# Module_Current_Probe_v2.net
KiCad netlist of a schematic drawn in EAGLE
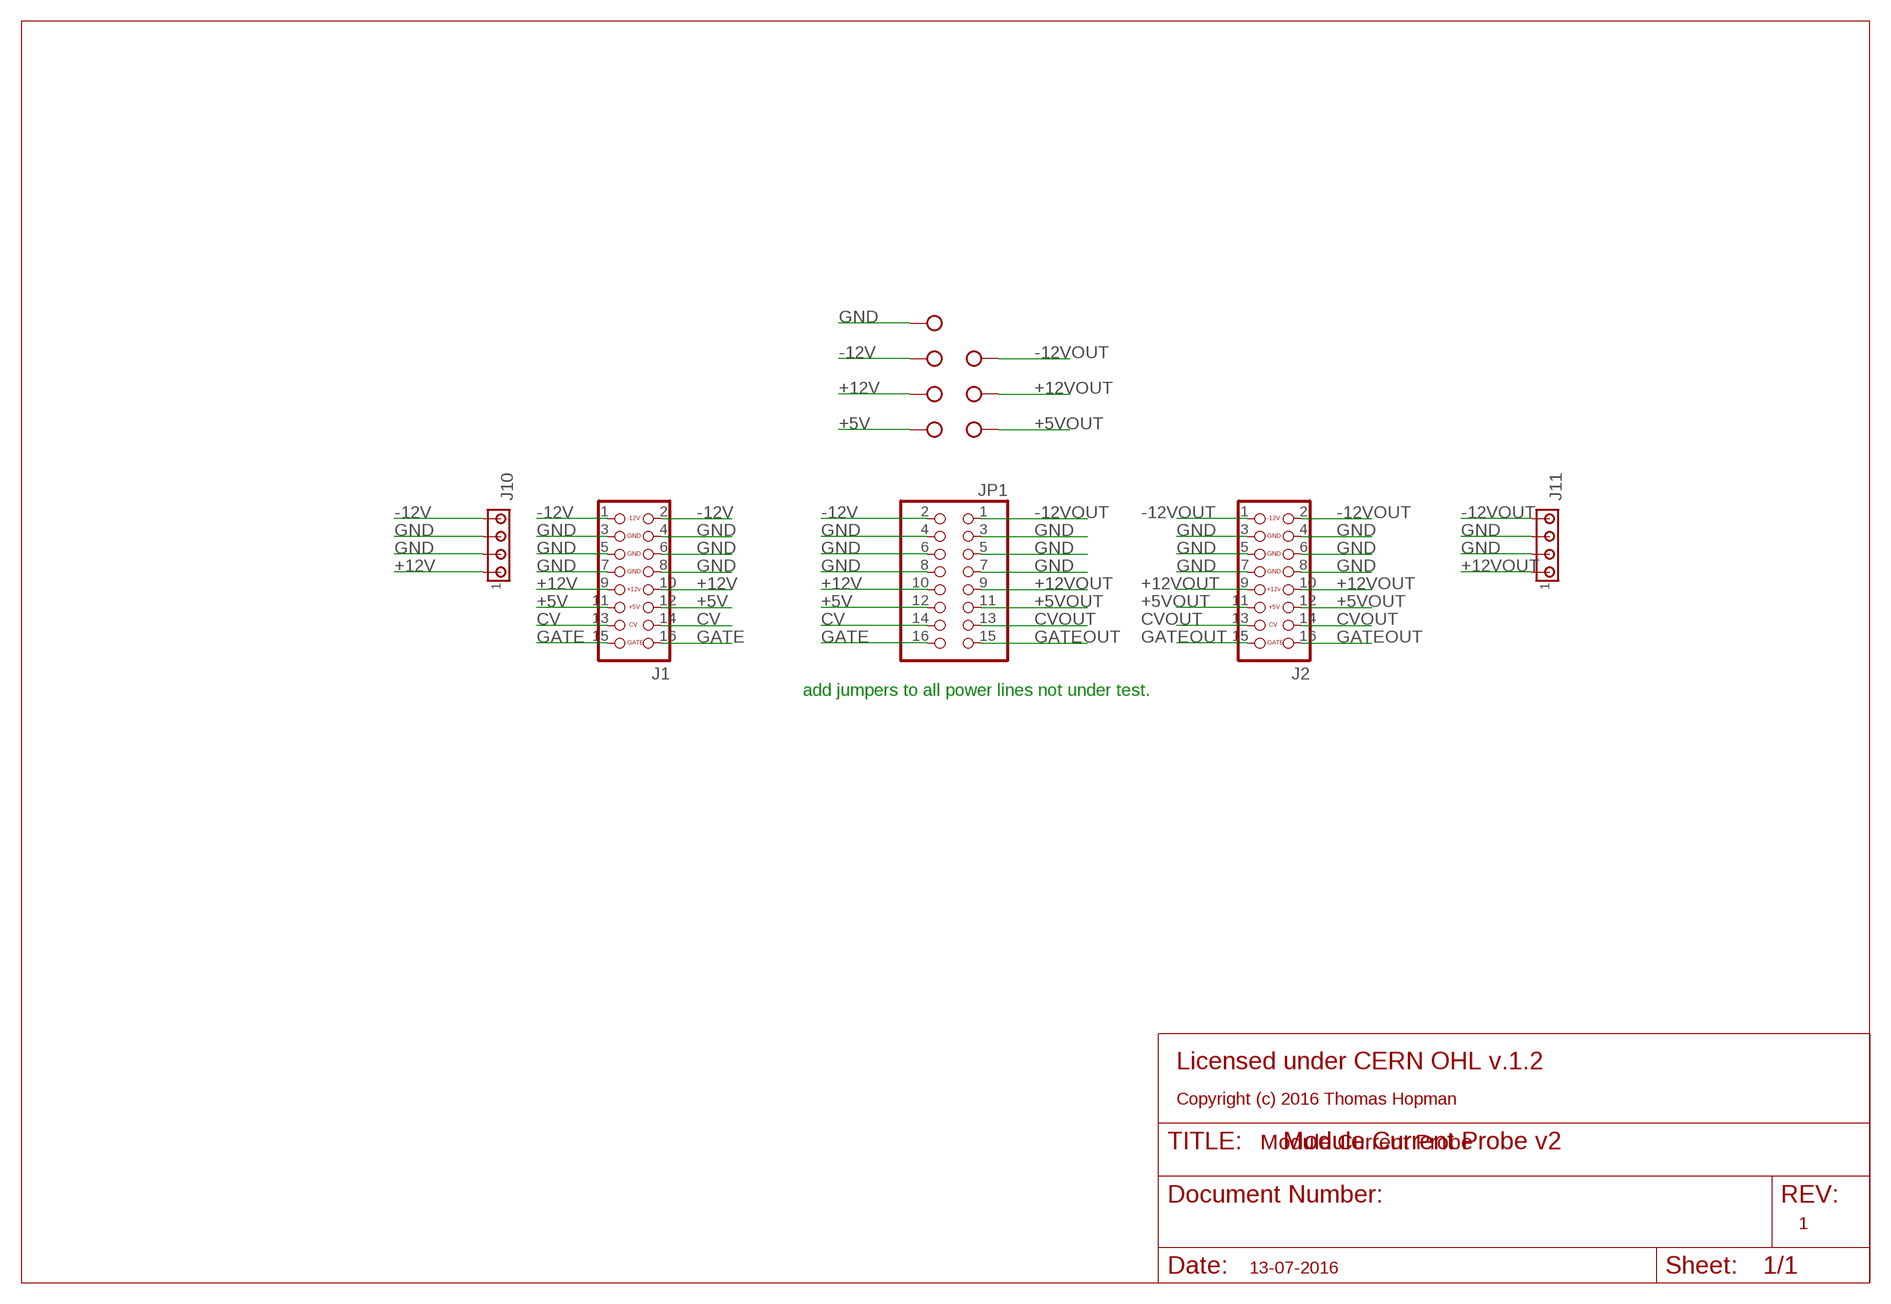
[diagram p0: schematic, sheet 1]

(export (version "E")
  (design (tool "Eeschema 10.0.6"))
  (components
    (comp (ref "J1")
      (value "CON_HEADER_2X08-PTH-SHROUDED")
      (footprint "eagle-import:PINSHRD_PTH_2X08")
      (libsource (lib "eagle-import") (part "CON_HEADER_2X08-PTH-SHROUDED"))
    )
    (comp (ref "J2")
      (value "CON_HEADER_2X08-PTH-SHROUDED")
      (footprint "eagle-import:PINSHRD_PTH_2X08")
      (libsource (lib "eagle-import") (part "CON_HEADER_2X08-PTH-SHROUDED"))
    )
    (comp (ref "J3")
      (value "BANANA-JACK")
      (footprint "eagle-import:BANANA-PRINT")
      (libsource (lib "eagle-import") (part "BANANA-JACK"))
    )
    (comp (ref "J4")
      (value "BANANA-JACK")
      (footprint "eagle-import:BANANA-PRINT")
      (libsource (lib "eagle-import") (part "BANANA-JACK"))
    )
    (comp (ref "J5")
      (value "BANANA-JACK")
      (footprint "eagle-import:BANANA-PRINT")
      (libsource (lib "eagle-import") (part "BANANA-JACK"))
    )
    (comp (ref "J6")
      (value "BANANA-JACK")
      (footprint "eagle-import:BANANA-PRINT")
      (libsource (lib "eagle-import") (part "BANANA-JACK"))
    )
    (comp (ref "J7")
      (value "BANANA-JACK")
      (footprint "eagle-import:BANANA-PRINT")
      (libsource (lib "eagle-import") (part "BANANA-JACK"))
    )
    (comp (ref "J8")
      (value "BANANA-JACK")
      (footprint "eagle-import:BANANA-PRINT")
      (libsource (lib "eagle-import") (part "BANANA-JACK"))
    )
    (comp (ref "J9")
      (value "BANANA-JACK")
      (footprint "eagle-import:BANANA-PRINT")
      (libsource (lib "eagle-import") (part "BANANA-JACK"))
    )
    (comp (ref "J10")
      (value "MTA04-156")
      (footprint "eagle-import:1X4MTA")
      (libsource (lib "eagle-import") (part "MTA04-156"))
    )
    (comp (ref "J11")
      (value "MTA04-156")
      (footprint "eagle-import:1X4MTA")
      (libsource (lib "eagle-import") (part "MTA04-156"))
    )
    (comp (ref "JP1")
      (value "PINHD-2X8")
      (footprint "eagle-import:2X08")
      (libsource (lib "eagle-import") (part "PINHD-2X8"))
    )
  )
  (nets
    (net (code "1") (name "/+5V") (class "Default")
      (node (ref "J1") (pin "11") (pinfunction "11_11") (pintype "passive"))
      (node (ref "J1") (pin "12") (pinfunction "12_12") (pintype "passive"))
      (node (ref "J5") (pin "P$1") (pinfunction "PIN_P$1") (pintype "bidirectional"))
      (node (ref "JP1") (pin "12") (pinfunction "12_12") (pintype "passive"))
    )
    (net (code "2") (name "/+5VOUT") (class "Default")
      (node (ref "J2") (pin "11") (pinfunction "11_11") (pintype "passive"))
      (node (ref "J2") (pin "12") (pinfunction "12_12") (pintype "passive"))
      (node (ref "J8") (pin "P$1") (pinfunction "PIN_P$1") (pintype "bidirectional"))
      (node (ref "JP1") (pin "11") (pinfunction "11_11") (pintype "passive"))
    )
    (net (code "3") (name "/+12V") (class "Default")
      (node (ref "J1") (pin "10") (pinfunction "10_10") (pintype "passive"))
      (node (ref "J1") (pin "9") (pinfunction "9_9") (pintype "passive"))
      (node (ref "J10") (pin "1") (pinfunction "1_1") (pintype "passive"))
      (node (ref "J4") (pin "P$1") (pinfunction "PIN_P$1") (pintype "bidirectional"))
      (node (ref "JP1") (pin "10") (pinfunction "10_10") (pintype "passive"))
    )
    (net (code "4") (name "/+12VOUT") (class "Default")
      (node (ref "J11") (pin "1") (pinfunction "1_1") (pintype "passive"))
      (node (ref "J2") (pin "10") (pinfunction "10_10") (pintype "passive"))
      (node (ref "J2") (pin "9") (pinfunction "9_9") (pintype "passive"))
      (node (ref "J7") (pin "P$1") (pinfunction "PIN_P$1") (pintype "bidirectional"))
      (node (ref "JP1") (pin "9") (pinfunction "9_9") (pintype "passive"))
    )
    (net (code "5") (name "/-12V") (class "Default")
      (node (ref "J1") (pin "1") (pinfunction "1_1") (pintype "passive"))
      (node (ref "J1") (pin "2") (pinfunction "2_2") (pintype "passive"))
      (node (ref "J10") (pin "4") (pinfunction "4_4") (pintype "passive"))
      (node (ref "J3") (pin "P$1") (pinfunction "PIN_P$1") (pintype "bidirectional"))
      (node (ref "JP1") (pin "2") (pinfunction "2_2") (pintype "passive"))
    )
    (net (code "6") (name "/-12VOUT") (class "Default")
      (node (ref "J11") (pin "4") (pinfunction "4_4") (pintype "passive"))
      (node (ref "J2") (pin "1") (pinfunction "1_1") (pintype "passive"))
      (node (ref "J2") (pin "2") (pinfunction "2_2") (pintype "passive"))
      (node (ref "J6") (pin "P$1") (pinfunction "PIN_P$1") (pintype "bidirectional"))
      (node (ref "JP1") (pin "1") (pinfunction "1_1") (pintype "passive"))
    )
    (net (code "7") (name "/CV") (class "Default")
      (node (ref "J1") (pin "13") (pinfunction "13_13") (pintype "passive"))
      (node (ref "J1") (pin "14") (pinfunction "14_14") (pintype "passive"))
      (node (ref "JP1") (pin "14") (pinfunction "14_14") (pintype "passive"))
    )
    (net (code "8") (name "/CVOUT") (class "Default")
      (node (ref "J2") (pin "13") (pinfunction "13_13") (pintype "passive"))
      (node (ref "J2") (pin "14") (pinfunction "14_14") (pintype "passive"))
      (node (ref "JP1") (pin "13") (pinfunction "13_13") (pintype "passive"))
    )
    (net (code "9") (name "/GATE") (class "Default")
      (node (ref "J1") (pin "15") (pinfunction "15_15") (pintype "passive"))
      (node (ref "J1") (pin "16") (pinfunction "16_16") (pintype "passive"))
      (node (ref "JP1") (pin "16") (pinfunction "16_16") (pintype "passive"))
    )
    (net (code "10") (name "/GATEOUT") (class "Default")
      (node (ref "J2") (pin "15") (pinfunction "15_15") (pintype "passive"))
      (node (ref "J2") (pin "16") (pinfunction "16_16") (pintype "passive"))
      (node (ref "JP1") (pin "15") (pinfunction "15_15") (pintype "passive"))
    )
    (net (code "11") (name "/GND") (class "Default")
      (node (ref "J1") (pin "3") (pinfunction "3_3") (pintype "passive"))
      (node (ref "J1") (pin "4") (pinfunction "4_4") (pintype "passive"))
      (node (ref "J1") (pin "5") (pinfunction "5_5") (pintype "passive"))
      (node (ref "J1") (pin "6") (pinfunction "6_6") (pintype "passive"))
      (node (ref "J1") (pin "7") (pinfunction "7_7") (pintype "passive"))
      (node (ref "J1") (pin "8") (pinfunction "8_8") (pintype "passive"))
      (node (ref "J10") (pin "2") (pinfunction "2_2") (pintype "passive"))
      (node (ref "J10") (pin "3") (pinfunction "3_3") (pintype "passive"))
      (node (ref "J11") (pin "2") (pinfunction "2_2") (pintype "passive"))
      (node (ref "J11") (pin "3") (pinfunction "3_3") (pintype "passive"))
      (node (ref "J2") (pin "3") (pinfunction "3_3") (pintype "passive"))
      (node (ref "J2") (pin "4") (pinfunction "4_4") (pintype "passive"))
      (node (ref "J2") (pin "5") (pinfunction "5_5") (pintype "passive"))
      (node (ref "J2") (pin "6") (pinfunction "6_6") (pintype "passive"))
      (node (ref "J2") (pin "7") (pinfunction "7_7") (pintype "passive"))
      (node (ref "J2") (pin "8") (pinfunction "8_8") (pintype "passive"))
      (node (ref "J9") (pin "P$1") (pinfunction "PIN_P$1") (pintype "bidirectional"))
      (node (ref "JP1") (pin "3") (pinfunction "3_3") (pintype "passive"))
      (node (ref "JP1") (pin "4") (pinfunction "4_4") (pintype "passive"))
      (node (ref "JP1") (pin "5") (pinfunction "5_5") (pintype "passive"))
      (node (ref "JP1") (pin "6") (pinfunction "6_6") (pintype "passive"))
      (node (ref "JP1") (pin "7") (pinfunction "7_7") (pintype "passive"))
      (node (ref "JP1") (pin "8") (pinfunction "8_8") (pintype "passive"))
    )
  )
)
